# Sheet1.net
KiCad netlist of a schematic drawn in Altium Designer
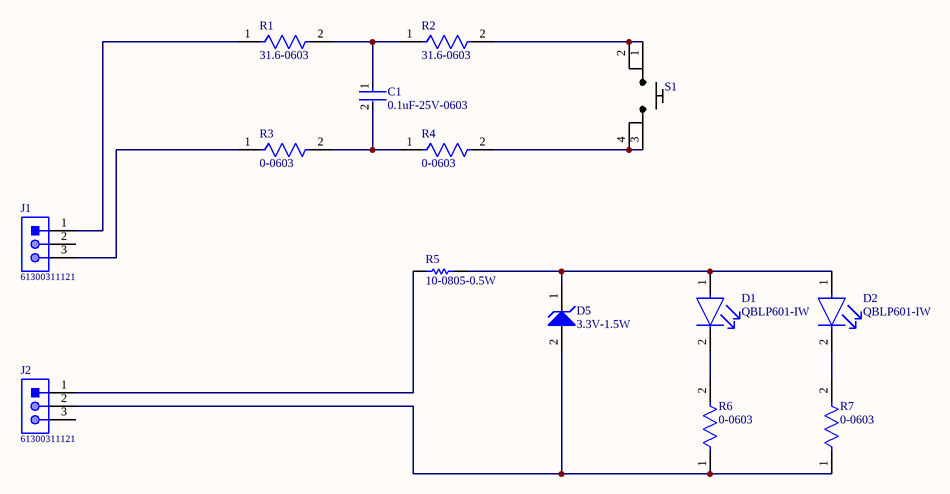
[diagram p0: Sheet1.SchDoc]

(export (version "E")
  (design (tool "Eeschema 10.0.6"))
  (components
    (comp (ref "C1")
      (value "0.1uF-25V-0603")
      (footprint "FP-C0603C-CF-MFG")
      (description "CAP CER 0.1UF 25V X7R 0603")
      (fields
        (field (name "OCTOPART") "https://octopart.com/c0603c104k3rac7411-kemet-9138804")
        (field (name "MANUFACTURER") "KEMET")
      )
      (libsource (lib "Altium Content Vault") (part "b4654b650e69147ec39a6b967a45e02"))
    )
    (comp (ref "D1")
      (value "QBLP601-IW")
      (footprint "FP-QBLP601-IW-MFG")
      (description "LED WHITE CLEAR 0603 SMD")
      (libsource (lib "Altium Content Vault") (part "ab1c01a81903e929fc6c44469aada92"))
    )
    (comp (ref "D2")
      (value "QBLP601-IW")
      (footprint "FP-QBLP601-IW-MFG")
      (description "LED WHITE CLEAR 0603 SMD")
      (libsource (lib "Altium Content Vault") (part "ab1c01a81903e929fc6c44469aada92"))
    )
    (comp (ref "D5")
      (value "3.3V-1.5W")
      (footprint "ONSC-SMA-2-403D-02_F_V")
      (description "1.5 W Zener Voltage Regulator, 2-Pin SMA, Pb-Free, Tape and Reel")
      (fields (field (name "MANUFACTURER") "On Semiconductor") (field (name "PARTNUMBER") "1SMA5920BT3G"))
      (libsource (lib "Schlib1") (part "CMP-1060-00079-2"))
    )
    (comp (ref "J1")
      (value "61300311121")
      (footprint "61300311121")
      (description "THT Vertical Pin Header WR-PHD, Pitch 2.54 mm, Single Row, 3 pins")
      (fields (field (name "MANUFACTURER") "Wurth Elektronik") (field (name "PUBLISHER") "WurthElektronik"))
      (libsource (lib "Altium Content Vault") (part "WE-CN-1P-M-R3"))
    )
    (comp (ref "J2")
      (value "61300311121")
      (footprint "61300311121")
      (description "THT Vertical Pin Header WR-PHD, Pitch 2.54 mm, Single Row, 3 pins")
      (fields (field (name "MANUFACTURER") "Wurth Elektronik") (field (name "PUBLISHER") "WurthElektronik"))
      (libsource (lib "Altium Content Vault") (part "WE-CN-1P-M-R3"))
    )
    (comp (ref "R1")
      (value "31.6-0603")
      (footprint "FP-RT0603-IPC_A")
      (description "RT0603 31.6Ω 0.1W 25 ppm/°C 0.50%")
      (fields (field (name "MANUFACTURER PART NUMBER") "RT0603DRD0731R6L"))
      (libsource (lib "Altium Content Vault") (part "1029c3af85768c4190bb7ad29bc67b5"))
    )
    (comp (ref "R2")
      (value "31.6-0603")
      (footprint "FP-RT0603-IPC_A")
      (description "RT0603 31.6Ω 0.1W 25 ppm/°C 0.50%")
      (fields (field (name "MANUFACTURER PART NUMBER") "RT0603DRD0731R6L"))
      (libsource (lib "Altium Content Vault") (part "1029c3af85768c4190bb7ad29bc67b5"))
    )
    (comp (ref "R3")
      (value "0-0603")
      (footprint "FP-RMCF0603-IPC_A")
      (description "0 Ohms Jumper 0.1W, 1/10W Chip Resistor 0603 (1608 Metric) Automotive AEC-Q200 Thick Film")
      (fields (field (name "MANUFACTURER PART NUMBER") "RMCF0603ZT0R00"))
      (libsource (lib "Altium Content Vault") (part "1029c3af85768c4190bb7ad29bc67b5"))
    )
    (comp (ref "R4")
      (value "0-0603")
      (footprint "FP-RMCF0603-IPC_A")
      (description "0 Ohms Jumper 0.1W, 1/10W Chip Resistor 0603 (1608 Metric) Automotive AEC-Q200 Thick Film")
      (fields (field (name "MANUFACTURER PART NUMBER") "RMCF0603ZT0R00"))
      (libsource (lib "Altium Content Vault") (part "1029c3af85768c4190bb7ad29bc67b5"))
    )
    (comp (ref "R5")
      (value "10-0805-0.5W")
      (footprint "RESC2013X70X40NL20T20")
      (fields (field (name "MANUFACTURER") "Panasonic") (field (name "PART NUMBER") "ERJ-P06J100V"))
      (libsource (lib "Altium Content Vault") (part "RES"))
    )
    (comp (ref "R6")
      (value "0-0603")
      (footprint "FP-RMCF0603-IPC_A")
      (description "0 Ohms Jumper 0.1W, 1/10W Chip Resistor 0603 (1608 Metric) Automotive AEC-Q200 Thick Film")
      (fields (field (name "MANUFACTURER PART NUMBER") "RMCF0603ZT0R00"))
      (libsource (lib "Altium Content Vault") (part "1029c3af85768c4190bb7ad29bc67b5"))
    )
    (comp (ref "R7")
      (value "0-0603")
      (footprint "FP-RMCF0603-IPC_A")
      (description "0 Ohms Jumper 0.1W, 1/10W Chip Resistor 0603 (1608 Metric) Automotive AEC-Q200 Thick Film")
      (fields (field (name "MANUFACTURER PART NUMBER") "RMCF0603ZT0R00"))
      (libsource (lib "Altium Content Vault") (part "1029c3af85768c4190bb7ad29bc67b5"))
    )
    (comp (ref "S1")
      (value "Switch")
      (footprint "E-Switch TL3305")
      (libsource (lib "Schlib1") (part "Switch"))
    )
  )
  (nets
    (net (code "1") (name "Net-(C1-Pad1)") (class "Default")
      (node (ref "C1") (pin "1") (pinfunction "1_1") (pintype "passive"))
      (node (ref "R1") (pin "2") (pinfunction "2_2") (pintype "passive"))
      (node (ref "R2") (pin "1") (pinfunction "1_1") (pintype "passive"))
    )
    (net (code "2") (name "Net-(C1-Pad2)") (class "Default")
      (node (ref "C1") (pin "2") (pinfunction "2_2") (pintype "passive"))
      (node (ref "R3") (pin "2") (pinfunction "2_2") (pintype "passive"))
      (node (ref "R4") (pin "1") (pinfunction "1_1") (pintype "passive"))
    )
    (net (code "3") (name "Net-(D1-A)") (class "Default")
      (node (ref "D1") (pin "1") (pinfunction "A_1") (pintype "passive"))
      (node (ref "D2") (pin "1") (pinfunction "A_1") (pintype "passive"))
      (node (ref "D5") (pin "1") (pinfunction "K_1") (pintype "passive"))
      (node (ref "R5") (pin "2") (pinfunction "2_2") (pintype "passive"))
    )
    (net (code "4") (name "Net-(D1-C)") (class "Default")
      (node (ref "D1") (pin "2") (pinfunction "C_2") (pintype "passive"))
      (node (ref "R6") (pin "2") (pinfunction "2_2") (pintype "passive"))
    )
    (net (code "5") (name "Net-(D2-C)") (class "Default")
      (node (ref "D2") (pin "2") (pinfunction "C_2") (pintype "passive"))
      (node (ref "R7") (pin "2") (pinfunction "2_2") (pintype "passive"))
    )
    (net (code "6") (name "Net-(D5-A)") (class "Default")
      (node (ref "D5") (pin "2") (pinfunction "A_2") (pintype "passive"))
      (node (ref "J2") (pin "2") (pinfunction "2_2") (pintype "passive"))
      (node (ref "R6") (pin "1") (pinfunction "1_1") (pintype "passive"))
      (node (ref "R7") (pin "1") (pinfunction "1_1") (pintype "passive"))
    )
    (net (code "7") (name "Net-(J1-Pad1)") (class "Default")
      (node (ref "J1") (pin "1") (pinfunction "1_1") (pintype "passive"))
      (node (ref "R1") (pin "1") (pinfunction "1_1") (pintype "passive"))
    )
    (net (code "8") (name "Net-(J1-Pad3)") (class "Default")
      (node (ref "J1") (pin "3") (pinfunction "3_3") (pintype "passive"))
      (node (ref "R3") (pin "1") (pinfunction "1_1") (pintype "passive"))
    )
    (net (code "9") (name "Net-(J2-Pad1)") (class "Default")
      (node (ref "J2") (pin "1") (pinfunction "1_1") (pintype "passive"))
      (node (ref "R5") (pin "1") (pinfunction "1_1") (pintype "passive"))
    )
    (net (code "10") (name "Net-(R2-Pad2)") (class "Default")
      (node (ref "R2") (pin "2") (pinfunction "2_2") (pintype "passive"))
      (node (ref "S1") (pin "1") (pinfunction "1_1") (pintype "passive"))
      (node (ref "S1") (pin "2") (pinfunction "2_2") (pintype "passive"))
    )
    (net (code "11") (name "Net-(R4-Pad2)") (class "Default")
      (node (ref "R4") (pin "2") (pinfunction "2_2") (pintype "passive"))
      (node (ref "S1") (pin "3") (pinfunction "3_3") (pintype "passive"))
      (node (ref "S1") (pin "4") (pinfunction "4_4") (pintype "passive"))
    )
    (net (code "12") (name "unconnected-(J1-Pad2)") (class "Default")
      (node (ref "J1") (pin "2") (pinfunction "2_2") (pintype "passive"))
    )
    (net (code "13") (name "unconnected-(J2-Pad3)") (class "Default")
      (node (ref "J2") (pin "3") (pinfunction "3_3") (pintype "passive"))
    )
  )
)
